# TTGO_shield_revB.net
KiCad netlist of a schematic drawn in EAGLE
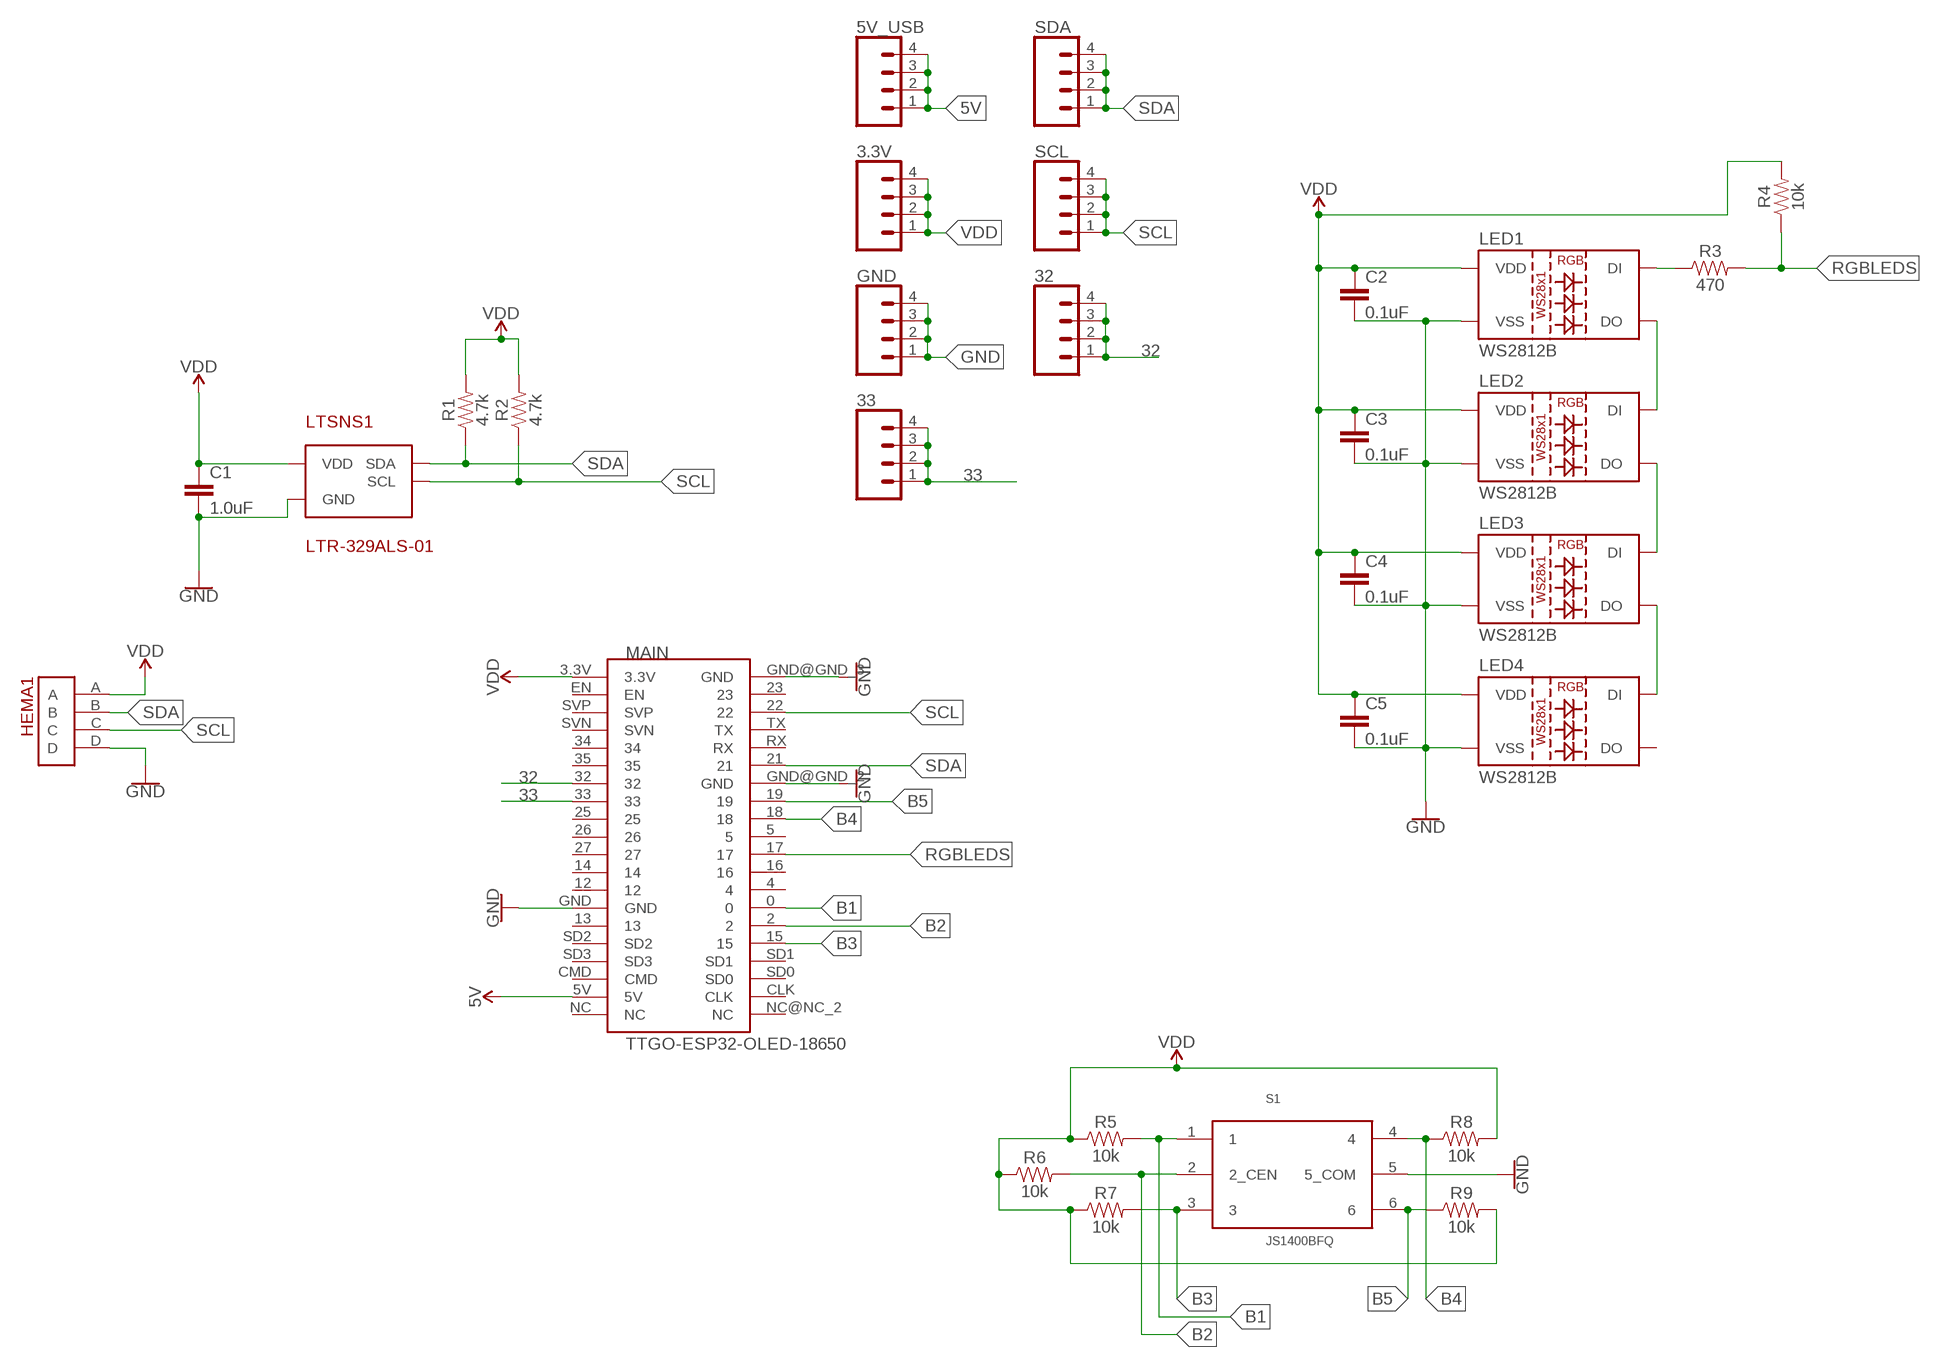
[diagram p0: schematic, sheet 1]

(export (version "E")
  (design (tool "Eeschema 10.0.6"))
  (components
    (comp (ref "3.3V")
      (value "CONN_041X04_NO_SILK")
      (footprint "eagle-import:1X04_NO_SILK")
      (libsource (lib "eagle-import") (part "CONN_041X04_NO_SILK"))
    )
    (comp (ref "5V_USB")
      (value "CONN_041X04_NO_SILK")
      (footprint "eagle-import:1X04_NO_SILK")
      (libsource (lib "eagle-import") (part "CONN_041X04_NO_SILK"))
    )
    (comp (ref "32")
      (value "CONN_041X04_NO_SILK")
      (footprint "eagle-import:1X04_NO_SILK")
      (libsource (lib "eagle-import") (part "CONN_041X04_NO_SILK"))
    )
    (comp (ref "33")
      (value "CONN_041X04_NO_SILK")
      (footprint "eagle-import:1X04_NO_SILK")
      (libsource (lib "eagle-import") (part "CONN_041X04_NO_SILK"))
    )
    (comp (ref "C1")
      (value "1.0uF")
      (footprint "eagle-import:0805")
      (libsource (lib "eagle-import") (part "1.0UF-0805-25V-10%"))
    )
    (comp (ref "C2")
      (value "0.1uF")
      (footprint "eagle-import:0603")
      (libsource (lib "eagle-import") (part "0.1UF-0603-25V-5%"))
    )
    (comp (ref "C3")
      (value "0.1uF")
      (footprint "eagle-import:0603")
      (libsource (lib "eagle-import") (part "0.1UF-0603-25V-5%"))
    )
    (comp (ref "C4")
      (value "0.1uF")
      (footprint "eagle-import:0603")
      (libsource (lib "eagle-import") (part "0.1UF-0603-25V-5%"))
    )
    (comp (ref "C5")
      (value "0.1uF")
      (footprint "eagle-import:0603")
      (libsource (lib "eagle-import") (part "0.1UF-0603-25V-5%"))
    )
    (comp (ref "GND")
      (value "CONN_041X04_NO_SILK")
      (footprint "eagle-import:1X04_NO_SILK")
      (libsource (lib "eagle-import") (part "CONN_041X04_NO_SILK"))
    )
    (comp (ref "HEMA1")
      (value "10120045-400LF")
      (footprint "eagle-import:10120045-400LF")
      (libsource (lib "eagle-import") (part "10120045-400LF"))
    )
    (comp (ref "LED1")
      (value "WS2812B")
      (footprint "eagle-import:WS2812B")
      (libsource (lib "eagle-import") (part "WS2812B"))
    )
    (comp (ref "LED2")
      (value "WS2812B")
      (footprint "eagle-import:WS2812B")
      (libsource (lib "eagle-import") (part "WS2812B"))
    )
    (comp (ref "LED3")
      (value "WS2812B")
      (footprint "eagle-import:WS2812B")
      (libsource (lib "eagle-import") (part "WS2812B"))
    )
    (comp (ref "LED4")
      (value "WS2812B")
      (footprint "eagle-import:WS2812B")
      (libsource (lib "eagle-import") (part "WS2812B"))
    )
    (comp (ref "LTSNS1")
      (value "LTR-329ALS-01")
      (footprint "eagle-import:CHIPLED-4")
      (libsource (lib "eagle-import") (part "LTR-329ALS-01"))
    )
    (comp (ref "MAIN")
      (value "TTGO-ESP32-OLED-18650")
      (footprint "eagle-import:TTGO-ESP32-OLED-18650")
      (libsource (lib "eagle-import") (part "TTGO-ESP32-OLED-18650"))
    )
    (comp (ref "R1")
      (value "4.7k")
      (footprint "eagle-import:0603")
      (libsource (lib "eagle-import") (part "4.7KOHM-0603-1/10W-1%"))
    )
    (comp (ref "R2")
      (value "4.7k")
      (footprint "eagle-import:0603")
      (libsource (lib "eagle-import") (part "4.7KOHM-0603-1/10W-1%"))
    )
    (comp (ref "R3")
      (value "470")
      (footprint "eagle-import:0603")
      (libsource (lib "eagle-import") (part "470OHM-0603-1/10W-1%"))
    )
    (comp (ref "R4")
      (value "10k")
      (footprint "eagle-import:0603")
      (libsource (lib "eagle-import") (part "10KOHM-0603-1/10W-1%"))
    )
    (comp (ref "R5")
      (value "10k")
      (footprint "eagle-import:0603")
      (libsource (lib "eagle-import") (part "10KOHM-0603-1/10W-1%"))
    )
    (comp (ref "R6")
      (value "10k")
      (footprint "eagle-import:0603")
      (libsource (lib "eagle-import") (part "10KOHM-0603-1/10W-1%"))
    )
    (comp (ref "R7")
      (value "10k")
      (footprint "eagle-import:0603")
      (libsource (lib "eagle-import") (part "10KOHM-0603-1/10W-1%"))
    )
    (comp (ref "R8")
      (value "10k")
      (footprint "eagle-import:0603")
      (libsource (lib "eagle-import") (part "10KOHM-0603-1/10W-1%"))
    )
    (comp (ref "R9")
      (value "10k")
      (footprint "eagle-import:0603")
      (libsource (lib "eagle-import") (part "10KOHM-0603-1/10W-1%"))
    )
    (comp (ref "S1")
      (value "JS1400BFQ")
      (footprint "eagle-import:JS1400BFQ")
      (libsource (lib "eagle-import") (part "JS1400BFQ"))
    )
    (comp (ref "SCL")
      (value "CONN_041X04_NO_SILK")
      (footprint "eagle-import:1X04_NO_SILK")
      (libsource (lib "eagle-import") (part "CONN_041X04_NO_SILK"))
    )
    (comp (ref "SDA")
      (value "CONN_041X04_NO_SILK")
      (footprint "eagle-import:1X04_NO_SILK")
      (libsource (lib "eagle-import") (part "CONN_041X04_NO_SILK"))
    )
  )
  (nets
    (net (code "1") (name "/32") (class "Default")
      (node (ref "32") (pin "1") (pinfunction "1_1") (pintype "passive"))
      (node (ref "32") (pin "2") (pinfunction "2_2") (pintype "passive"))
      (node (ref "32") (pin "3") (pinfunction "3_3") (pintype "passive"))
      (node (ref "32") (pin "4") (pinfunction "4_4") (pintype "passive"))
      (node (ref "MAIN") (pin "32") (pinfunction "32_32") (pintype "bidirectional"))
    )
    (net (code "2") (name "/33") (class "Default")
      (node (ref "33") (pin "1") (pinfunction "1_1") (pintype "passive"))
      (node (ref "33") (pin "2") (pinfunction "2_2") (pintype "passive"))
      (node (ref "33") (pin "3") (pinfunction "3_3") (pintype "passive"))
      (node (ref "33") (pin "4") (pinfunction "4_4") (pintype "passive"))
      (node (ref "MAIN") (pin "33") (pinfunction "33_33") (pintype "bidirectional"))
    )
    (net (code "3") (name "5V") (class "Default")
      (node (ref "5V_USB") (pin "1") (pinfunction "1_1") (pintype "passive"))
      (node (ref "5V_USB") (pin "2") (pinfunction "2_2") (pintype "passive"))
      (node (ref "5V_USB") (pin "3") (pinfunction "3_3") (pintype "passive"))
      (node (ref "5V_USB") (pin "4") (pinfunction "4_4") (pintype "passive"))
      (node (ref "MAIN") (pin "5V") (pinfunction "5V_5V") (pintype "bidirectional"))
    )
    (net (code "4") (name "B1") (class "Default")
      (node (ref "MAIN") (pin "0") (pinfunction "0_0") (pintype "bidirectional"))
      (node (ref "R5") (pin "2") (pinfunction "2_2") (pintype "passive"))
      (node (ref "S1") (pin "1") (pinfunction "1_1") (pintype "bidirectional"))
    )
    (net (code "5") (name "B2") (class "Default")
      (node (ref "MAIN") (pin "2") (pinfunction "2_2") (pintype "bidirectional"))
      (node (ref "R6") (pin "2") (pinfunction "2_2") (pintype "passive"))
      (node (ref "S1") (pin "2") (pinfunction "2_CEN_2") (pintype "bidirectional"))
    )
    (net (code "6") (name "B3") (class "Default")
      (node (ref "MAIN") (pin "15") (pinfunction "15_15") (pintype "bidirectional"))
      (node (ref "R7") (pin "2") (pinfunction "2_2") (pintype "passive"))
      (node (ref "S1") (pin "3") (pinfunction "3_3") (pintype "bidirectional"))
    )
    (net (code "7") (name "B4") (class "Default")
      (node (ref "MAIN") (pin "18") (pinfunction "18_18") (pintype "bidirectional"))
      (node (ref "R8") (pin "1") (pinfunction "1_1") (pintype "passive"))
      (node (ref "S1") (pin "4") (pinfunction "4_4") (pintype "bidirectional"))
    )
    (net (code "8") (name "B5") (class "Default")
      (node (ref "MAIN") (pin "19") (pinfunction "19_19") (pintype "bidirectional"))
      (node (ref "R9") (pin "1") (pinfunction "1_1") (pintype "passive"))
      (node (ref "S1") (pin "6") (pinfunction "6_6") (pintype "bidirectional"))
    )
    (net (code "9") (name "GND") (class "Default")
      (node (ref "C1") (pin "2") (pinfunction "2_2") (pintype "passive"))
      (node (ref "C2") (pin "2") (pinfunction "2_2") (pintype "passive"))
      (node (ref "C3") (pin "2") (pinfunction "2_2") (pintype "passive"))
      (node (ref "C4") (pin "2") (pinfunction "2_2") (pintype "passive"))
      (node (ref "C5") (pin "2") (pinfunction "2_2") (pintype "passive"))
      (node (ref "GND") (pin "1") (pinfunction "1_1") (pintype "passive"))
      (node (ref "GND") (pin "2") (pinfunction "2_2") (pintype "passive"))
      (node (ref "GND") (pin "3") (pinfunction "3_3") (pintype "passive"))
      (node (ref "GND") (pin "4") (pinfunction "4_4") (pintype "passive"))
      (node (ref "HEMA1") (pin "D") (pinfunction "D_D") (pintype "bidirectional"))
      (node (ref "LED1") (pin "3") (pinfunction "VSS_3") (pintype "bidirectional"))
      (node (ref "LED2") (pin "3") (pinfunction "VSS_3") (pintype "bidirectional"))
      (node (ref "LED3") (pin "3") (pinfunction "VSS_3") (pintype "bidirectional"))
      (node (ref "LED4") (pin "3") (pinfunction "VSS_3") (pintype "bidirectional"))
      (node (ref "LTSNS1") (pin "2") (pinfunction "GND_2") (pintype "bidirectional"))
      (node (ref "MAIN") (pin "GND") (pinfunction "GND_GND") (pintype "bidirectional"))
      (node (ref "MAIN") (pin "GND@GND_2") (pinfunction "GND_GND@GND_2") (pintype "bidirectional"))
      (node (ref "MAIN") (pin "GND@GND_3") (pinfunction "GND_GND@GND_3") (pintype "bidirectional"))
      (node (ref "S1") (pin "5") (pinfunction "5_COM_5") (pintype "bidirectional"))
    )
    (net (code "10") (name "Net-(LED1-DI)") (class "Default")
      (node (ref "LED1") (pin "4") (pinfunction "DI_4") (pintype "bidirectional"))
      (node (ref "R3") (pin "1") (pinfunction "1_1") (pintype "passive"))
    )
    (net (code "11") (name "Net-(LED1-DO)") (class "Default")
      (node (ref "LED1") (pin "2") (pinfunction "DO_2") (pintype "bidirectional"))
      (node (ref "LED2") (pin "4") (pinfunction "DI_4") (pintype "bidirectional"))
    )
    (net (code "12") (name "Net-(LED2-DO)") (class "Default")
      (node (ref "LED2") (pin "2") (pinfunction "DO_2") (pintype "bidirectional"))
      (node (ref "LED3") (pin "4") (pinfunction "DI_4") (pintype "bidirectional"))
    )
    (net (code "13") (name "Net-(LED3-DO)") (class "Default")
      (node (ref "LED3") (pin "2") (pinfunction "DO_2") (pintype "bidirectional"))
      (node (ref "LED4") (pin "4") (pinfunction "DI_4") (pintype "bidirectional"))
    )
    (net (code "14") (name "RGBLEDS") (class "Default")
      (node (ref "MAIN") (pin "17") (pinfunction "17_17") (pintype "bidirectional"))
      (node (ref "R3") (pin "2") (pinfunction "2_2") (pintype "passive"))
      (node (ref "R4") (pin "1") (pinfunction "1_1") (pintype "passive"))
    )
    (net (code "15") (name "SCL") (class "Default")
      (node (ref "HEMA1") (pin "C") (pinfunction "C_C") (pintype "bidirectional"))
      (node (ref "LTSNS1") (pin "4") (pinfunction "SCL_4") (pintype "bidirectional"))
      (node (ref "MAIN") (pin "22") (pinfunction "22_22") (pintype "bidirectional"))
      (node (ref "R2") (pin "1") (pinfunction "1_1") (pintype "passive"))
      (node (ref "SCL") (pin "1") (pinfunction "1_1") (pintype "passive"))
      (node (ref "SCL") (pin "2") (pinfunction "2_2") (pintype "passive"))
      (node (ref "SCL") (pin "3") (pinfunction "3_3") (pintype "passive"))
      (node (ref "SCL") (pin "4") (pinfunction "4_4") (pintype "passive"))
    )
    (net (code "16") (name "SDA") (class "Default")
      (node (ref "HEMA1") (pin "B") (pinfunction "B_B") (pintype "bidirectional"))
      (node (ref "LTSNS1") (pin "3") (pinfunction "SDA_3") (pintype "bidirectional"))
      (node (ref "MAIN") (pin "21") (pinfunction "21_21") (pintype "bidirectional"))
      (node (ref "R1") (pin "1") (pinfunction "1_1") (pintype "passive"))
      (node (ref "SDA") (pin "1") (pinfunction "1_1") (pintype "passive"))
      (node (ref "SDA") (pin "2") (pinfunction "2_2") (pintype "passive"))
      (node (ref "SDA") (pin "3") (pinfunction "3_3") (pintype "passive"))
      (node (ref "SDA") (pin "4") (pinfunction "4_4") (pintype "passive"))
    )
    (net (code "17") (name "VDD") (class "Default")
      (node (ref "3.3V") (pin "1") (pinfunction "1_1") (pintype "passive"))
      (node (ref "3.3V") (pin "2") (pinfunction "2_2") (pintype "passive"))
      (node (ref "3.3V") (pin "3") (pinfunction "3_3") (pintype "passive"))
      (node (ref "3.3V") (pin "4") (pinfunction "4_4") (pintype "passive"))
      (node (ref "C1") (pin "1") (pinfunction "1_1") (pintype "passive"))
      (node (ref "C2") (pin "1") (pinfunction "1_1") (pintype "passive"))
      (node (ref "C3") (pin "1") (pinfunction "1_1") (pintype "passive"))
      (node (ref "C4") (pin "1") (pinfunction "1_1") (pintype "passive"))
      (node (ref "C5") (pin "1") (pinfunction "1_1") (pintype "passive"))
      (node (ref "HEMA1") (pin "A") (pinfunction "A_A") (pintype "bidirectional"))
      (node (ref "LED1") (pin "1") (pinfunction "VDD_1") (pintype "bidirectional"))
      (node (ref "LED2") (pin "1") (pinfunction "VDD_1") (pintype "bidirectional"))
      (node (ref "LED3") (pin "1") (pinfunction "VDD_1") (pintype "bidirectional"))
      (node (ref "LED4") (pin "1") (pinfunction "VDD_1") (pintype "bidirectional"))
      (node (ref "LTSNS1") (pin "1") (pinfunction "VDD_1") (pintype "bidirectional"))
      (node (ref "MAIN") (pin "3.3V") (pinfunction "3.3V_3.3V") (pintype "bidirectional"))
      (node (ref "R1") (pin "2") (pinfunction "2_2") (pintype "passive"))
      (node (ref "R2") (pin "2") (pinfunction "2_2") (pintype "passive"))
      (node (ref "R4") (pin "2") (pinfunction "2_2") (pintype "passive"))
      (node (ref "R5") (pin "1") (pinfunction "1_1") (pintype "passive"))
      (node (ref "R6") (pin "1") (pinfunction "1_1") (pintype "passive"))
      (node (ref "R7") (pin "1") (pinfunction "1_1") (pintype "passive"))
      (node (ref "R8") (pin "2") (pinfunction "2_2") (pintype "passive"))
      (node (ref "R9") (pin "2") (pinfunction "2_2") (pintype "passive"))
    )
    (net (code "18") (name "unconnected-(LED4-DO-Pad2)") (class "Default")
      (node (ref "LED4") (pin "2") (pinfunction "DO_2") (pintype "bidirectional"))
    )
    (net (code "19") (name "unconnected-(MAIN-NC-PadNC@NC_2)") (class "Default")
      (node (ref "MAIN") (pin "NC@NC_2") (pinfunction "NC_NC@NC_2") (pintype "bidirectional"))
    )
    (net (code "20") (name "unconnected-(MAIN-Pad4)") (class "Default")
      (node (ref "MAIN") (pin "4") (pinfunction "4_4") (pintype "bidirectional"))
    )
    (net (code "21") (name "unconnected-(MAIN-Pad5)") (class "Default")
      (node (ref "MAIN") (pin "5") (pinfunction "5_5") (pintype "bidirectional"))
    )
    (net (code "22") (name "unconnected-(MAIN-Pad12)") (class "Default")
      (node (ref "MAIN") (pin "12") (pinfunction "12_12") (pintype "bidirectional"))
    )
    (net (code "23") (name "unconnected-(MAIN-Pad13)") (class "Default")
      (node (ref "MAIN") (pin "13") (pinfunction "13_13") (pintype "bidirectional"))
    )
    (net (code "24") (name "unconnected-(MAIN-Pad14)") (class "Default")
      (node (ref "MAIN") (pin "14") (pinfunction "14_14") (pintype "bidirectional"))
    )
    (net (code "25") (name "unconnected-(MAIN-Pad16)") (class "Default")
      (node (ref "MAIN") (pin "16") (pinfunction "16_16") (pintype "bidirectional"))
    )
    (net (code "26") (name "unconnected-(MAIN-Pad23)") (class "Default")
      (node (ref "MAIN") (pin "23") (pinfunction "23_23") (pintype "bidirectional"))
    )
    (net (code "27") (name "unconnected-(MAIN-Pad25)") (class "Default")
      (node (ref "MAIN") (pin "25") (pinfunction "25_25") (pintype "bidirectional"))
    )
    (net (code "28") (name "unconnected-(MAIN-Pad26)") (class "Default")
      (node (ref "MAIN") (pin "26") (pinfunction "26_26") (pintype "bidirectional"))
    )
    (net (code "29") (name "unconnected-(MAIN-Pad27)") (class "Default")
      (node (ref "MAIN") (pin "27") (pinfunction "27_27") (pintype "bidirectional"))
    )
    (net (code "30") (name "unconnected-(MAIN-Pad34)") (class "Default")
      (node (ref "MAIN") (pin "34") (pinfunction "34_34") (pintype "bidirectional"))
    )
    (net (code "31") (name "unconnected-(MAIN-Pad35)") (class "Default")
      (node (ref "MAIN") (pin "35") (pinfunction "35_35") (pintype "bidirectional"))
    )
    (net (code "32") (name "unconnected-(MAIN-PadCLK)") (class "Default")
      (node (ref "MAIN") (pin "CLK") (pinfunction "CLK_CLK") (pintype "bidirectional"))
    )
    (net (code "33") (name "unconnected-(MAIN-PadCMD)") (class "Default")
      (node (ref "MAIN") (pin "CMD") (pinfunction "CMD_CMD") (pintype "bidirectional"))
    )
    (net (code "34") (name "unconnected-(MAIN-PadEN)") (class "Default")
      (node (ref "MAIN") (pin "EN") (pinfunction "EN_EN") (pintype "bidirectional"))
    )
    (net (code "35") (name "unconnected-(MAIN-PadNC)") (class "Default")
      (node (ref "MAIN") (pin "NC") (pinfunction "NC_NC") (pintype "bidirectional"))
    )
    (net (code "36") (name "unconnected-(MAIN-PadRX)") (class "Default")
      (node (ref "MAIN") (pin "RX") (pinfunction "RX_RX") (pintype "bidirectional"))
    )
    (net (code "37") (name "unconnected-(MAIN-PadSD0)") (class "Default")
      (node (ref "MAIN") (pin "SD0") (pinfunction "SD0_SD0") (pintype "bidirectional"))
    )
    (net (code "38") (name "unconnected-(MAIN-PadSD1)") (class "Default")
      (node (ref "MAIN") (pin "SD1") (pinfunction "SD1_SD1") (pintype "bidirectional"))
    )
    (net (code "39") (name "unconnected-(MAIN-PadSD2)") (class "Default")
      (node (ref "MAIN") (pin "SD2") (pinfunction "SD2_SD2") (pintype "bidirectional"))
    )
    (net (code "40") (name "unconnected-(MAIN-PadSD3)") (class "Default")
      (node (ref "MAIN") (pin "SD3") (pinfunction "SD3_SD3") (pintype "bidirectional"))
    )
    (net (code "41") (name "unconnected-(MAIN-PadSVN)") (class "Default")
      (node (ref "MAIN") (pin "SVN") (pinfunction "SVN_SVN") (pintype "bidirectional"))
    )
    (net (code "42") (name "unconnected-(MAIN-PadSVP)") (class "Default")
      (node (ref "MAIN") (pin "SVP") (pinfunction "SVP_SVP") (pintype "bidirectional"))
    )
    (net (code "43") (name "unconnected-(MAIN-PadTX)") (class "Default")
      (node (ref "MAIN") (pin "TX") (pinfunction "TX_TX") (pintype "bidirectional"))
    )
  )
)
